# LightStickControl.net
KiCad netlist of a schematic drawn in EAGLE
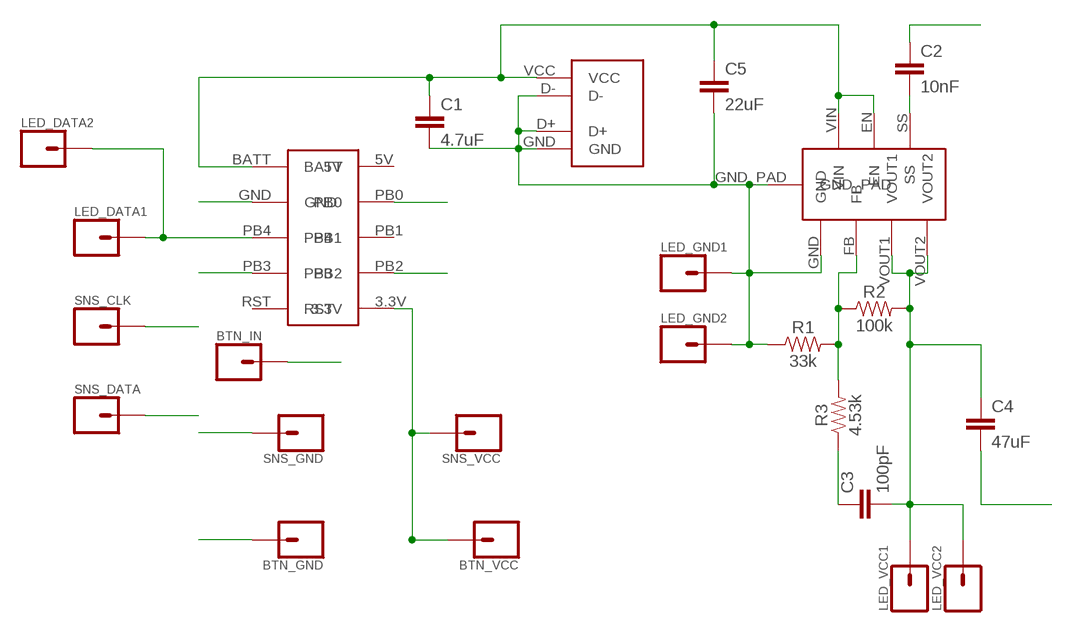
[diagram p0: schematic, sheet 1]

(export (version "E")
  (design (tool "Eeschema 10.0.6"))
  (components
    (comp (ref "BTN_GND")
      (value "CONN_01")
      (footprint "eagle-import:1X01")
      (libsource (lib "eagle-import") (part "CONN_01"))
    )
    (comp (ref "BTN_IN")
      (value "CONN_01")
      (footprint "eagle-import:1X01")
      (libsource (lib "eagle-import") (part "CONN_01"))
    )
    (comp (ref "BTN_VCC")
      (value "CONN_01")
      (footprint "eagle-import:1X01")
      (libsource (lib "eagle-import") (part "CONN_01"))
    )
    (comp (ref "C1")
      (value "4.7uF")
      (footprint "eagle-import:0603")
      (libsource (lib "eagle-import") (part "4.7UF0603"))
    )
    (comp (ref "C2")
      (value "10nF")
      (footprint "eagle-import:0603")
      (libsource (lib "eagle-import") (part "10NF-0603-50V-10%"))
    )
    (comp (ref "C3")
      (value "100pF")
      (footprint "eagle-import:0603")
      (libsource (lib "eagle-import") (part "100PF-0603-50V-5%"))
    )
    (comp (ref "C4")
      (value "47uF")
      (footprint "eagle-import:0805")
      (libsource (lib "eagle-import") (part "22UF-0805-6.3V-20%"))
    )
    (comp (ref "C5")
      (value "22uF")
      (footprint "eagle-import:0805")
      (libsource (lib "eagle-import") (part "22UF-0805-6.3V-20%"))
    )
    (comp (ref "LED_DATA1")
      (value "CONN_01")
      (footprint "eagle-import:1X01")
      (libsource (lib "eagle-import") (part "CONN_01"))
    )
    (comp (ref "LED_DATA2")
      (value "CONN_01")
      (footprint "eagle-import:1X01")
      (libsource (lib "eagle-import") (part "CONN_01"))
    )
    (comp (ref "LED_GND1")
      (value "CONN_01")
      (footprint "eagle-import:1X01")
      (libsource (lib "eagle-import") (part "CONN_01"))
    )
    (comp (ref "LED_GND2")
      (value "CONN_01")
      (footprint "eagle-import:1X01")
      (libsource (lib "eagle-import") (part "CONN_01"))
    )
    (comp (ref "LED_VCC1")
      (value "CONN_01")
      (footprint "eagle-import:1X01")
      (libsource (lib "eagle-import") (part "CONN_01"))
    )
    (comp (ref "LED_VCC2")
      (value "CONN_01")
      (footprint "eagle-import:1X01")
      (libsource (lib "eagle-import") (part "CONN_01"))
    )
    (comp (ref "MCU1")
      (value "ARDUINO_TRINKET")
      (footprint "eagle-import:ARDUINO_TRINKET")
      (libsource (lib "eagle-import") (part "ARDUINO_TRINKET"))
    )
    (comp (ref "R1")
      (value "33k")
      (footprint "eagle-import:0603")
      (libsource (lib "eagle-import") (part "33KOHM-0603-1/10W-1%"))
    )
    (comp (ref "R2")
      (value "100k")
      (footprint "eagle-import:0603")
      (libsource (lib "eagle-import") (part "100KOHM-0603-1/10W-1%"))
    )
    (comp (ref "R3")
      (value "4.53k")
      (footprint "eagle-import:0603")
      (libsource (lib "eagle-import") (part "4.7KOHM-0603-1/10W-1%"))
    )
    (comp (ref "SNS_CLK")
      (value "CONN_01")
      (footprint "eagle-import:1X01")
      (libsource (lib "eagle-import") (part "CONN_01"))
    )
    (comp (ref "SNS_DATA")
      (value "CONN_01")
      (footprint "eagle-import:1X01")
      (libsource (lib "eagle-import") (part "CONN_01"))
    )
    (comp (ref "SNS_GND")
      (value "CONN_01")
      (footprint "eagle-import:1X01")
      (libsource (lib "eagle-import") (part "CONN_01"))
    )
    (comp (ref "SNS_VCC")
      (value "CONN_01")
      (footprint "eagle-import:1X01")
      (libsource (lib "eagle-import") (part "CONN_01"))
    )
    (comp (ref "USB1")
      (value "USB_A_932")
      (footprint "eagle-import:USB_A_932")
      (libsource (lib "eagle-import") (part "USB_A_932"))
    )
    (comp (ref "V1")
      (value "LMZ10503")
      (footprint "eagle-import:TO-PMOD")
      (libsource (lib "eagle-import") (part "LMZ10503"))
    )
  )
  (nets
    (net (code "1") (name "/BTN_IN") (class "Default")
      (node (ref "BTN_IN") (pin "1") (pinfunction "1_1") (pintype "passive"))
      (node (ref "MCU1") (pin "PB3") (pinfunction "PB3_PB3") (pintype "bidirectional"))
    )
    (net (code "2") (name "/GND") (class "Default")
      (node (ref "BTN_GND") (pin "1") (pinfunction "1_1") (pintype "passive"))
      (node (ref "C1") (pin "2") (pinfunction "2_2") (pintype "passive"))
      (node (ref "C2") (pin "1") (pinfunction "1_1") (pintype "passive"))
      (node (ref "C4") (pin "2") (pinfunction "2_2") (pintype "passive"))
      (node (ref "C5") (pin "2") (pinfunction "2_2") (pintype "passive"))
      (node (ref "LED_GND1") (pin "1") (pinfunction "1_1") (pintype "passive"))
      (node (ref "LED_GND2") (pin "1") (pinfunction "1_1") (pintype "passive"))
      (node (ref "MCU1") (pin "GND") (pinfunction "GND_GND") (pintype "bidirectional"))
      (node (ref "R1") (pin "1") (pinfunction "1_1") (pintype "passive"))
      (node (ref "SNS_GND") (pin "1") (pinfunction "1_1") (pintype "passive"))
      (node (ref "USB1") (pin "D+") (pinfunction "D+_D+") (pintype "bidirectional"))
      (node (ref "USB1") (pin "D-") (pinfunction "D-_D-") (pintype "bidirectional"))
      (node (ref "USB1") (pin "GND") (pinfunction "GND_GND") (pintype "bidirectional"))
      (node (ref "V1") (pin "GND") (pinfunction "GND_GND") (pintype "bidirectional"))
      (node (ref "V1") (pin "GND_PAD") (pinfunction "GND_PAD_GND_PAD") (pintype "bidirectional"))
    )
    (net (code "3") (name "/SNS_CLK") (class "Default")
      (node (ref "MCU1") (pin "PB2") (pinfunction "PB2_PB2") (pintype "bidirectional"))
      (node (ref "SNS_CLK") (pin "1") (pinfunction "1_1") (pintype "passive"))
    )
    (net (code "4") (name "/SNS_DATA") (class "Default")
      (node (ref "MCU1") (pin "PB0") (pinfunction "PB0_PB0") (pintype "bidirectional"))
      (node (ref "SNS_DATA") (pin "1") (pinfunction "1_1") (pintype "passive"))
    )
    (net (code "5") (name "Net-(BTN_VCC-Pad1)") (class "Default")
      (node (ref "BTN_VCC") (pin "1") (pinfunction "1_1") (pintype "passive"))
      (node (ref "MCU1") (pin "3.3V") (pinfunction "3.3V_3.3V") (pintype "bidirectional"))
      (node (ref "SNS_VCC") (pin "1") (pinfunction "1_1") (pintype "passive"))
    )
    (net (code "6") (name "Net-(C1-Pad1)") (class "Default")
      (node (ref "C1") (pin "1") (pinfunction "1_1") (pintype "passive"))
      (node (ref "C5") (pin "1") (pinfunction "1_1") (pintype "passive"))
      (node (ref "MCU1") (pin "BATT") (pinfunction "BATT_BATT") (pintype "bidirectional"))
      (node (ref "USB1") (pin "VCC") (pinfunction "VCC_VCC") (pintype "bidirectional"))
      (node (ref "V1") (pin "EN") (pinfunction "EN_EN") (pintype "bidirectional"))
      (node (ref "V1") (pin "VIN") (pinfunction "VIN_VIN") (pintype "bidirectional"))
    )
    (net (code "7") (name "Net-(C2-Pad2)") (class "Default")
      (node (ref "C2") (pin "2") (pinfunction "2_2") (pintype "passive"))
      (node (ref "V1") (pin "SS") (pinfunction "SS_SS") (pintype "bidirectional"))
    )
    (net (code "8") (name "Net-(C3-Pad1)") (class "Default")
      (node (ref "C3") (pin "1") (pinfunction "1_1") (pintype "passive"))
      (node (ref "R3") (pin "1") (pinfunction "1_1") (pintype "passive"))
    )
    (net (code "9") (name "Net-(C3-Pad2)") (class "Default")
      (node (ref "C3") (pin "2") (pinfunction "2_2") (pintype "passive"))
      (node (ref "C4") (pin "1") (pinfunction "1_1") (pintype "passive"))
      (node (ref "LED_VCC1") (pin "1") (pinfunction "1_1") (pintype "passive"))
      (node (ref "LED_VCC2") (pin "1") (pinfunction "1_1") (pintype "passive"))
      (node (ref "R2") (pin "2") (pinfunction "2_2") (pintype "passive"))
      (node (ref "V1") (pin "VOUT1") (pinfunction "VOUT1_VOUT1") (pintype "bidirectional"))
      (node (ref "V1") (pin "VOUT2") (pinfunction "VOUT2_VOUT2") (pintype "bidirectional"))
    )
    (net (code "10") (name "Net-(LED_DATA1-Pad1)") (class "Default")
      (node (ref "LED_DATA1") (pin "1") (pinfunction "1_1") (pintype "passive"))
      (node (ref "LED_DATA2") (pin "1") (pinfunction "1_1") (pintype "passive"))
      (node (ref "MCU1") (pin "PB4") (pinfunction "PB4_PB4") (pintype "bidirectional"))
    )
    (net (code "11") (name "Net-(R1-Pad2)") (class "Default")
      (node (ref "R1") (pin "2") (pinfunction "2_2") (pintype "passive"))
      (node (ref "R2") (pin "1") (pinfunction "1_1") (pintype "passive"))
      (node (ref "R3") (pin "2") (pinfunction "2_2") (pintype "passive"))
      (node (ref "V1") (pin "FB") (pinfunction "FB_FB") (pintype "bidirectional"))
    )
    (net (code "12") (name "unconnected-(MCU1-Pad5V)") (class "Default")
      (node (ref "MCU1") (pin "5V") (pinfunction "5V_5V") (pintype "bidirectional"))
    )
    (net (code "13") (name "unconnected-(MCU1-PadPB1)") (class "Default")
      (node (ref "MCU1") (pin "PB1") (pinfunction "PB1_PB1") (pintype "bidirectional"))
    )
    (net (code "14") (name "unconnected-(MCU1-PadRST)") (class "Default")
      (node (ref "MCU1") (pin "RST") (pinfunction "RST_RST") (pintype "bidirectional"))
    )
  )
)
